# PC104Plus-ESP32-Module.net
KiCad netlist of a schematic drawn in Altium Designer
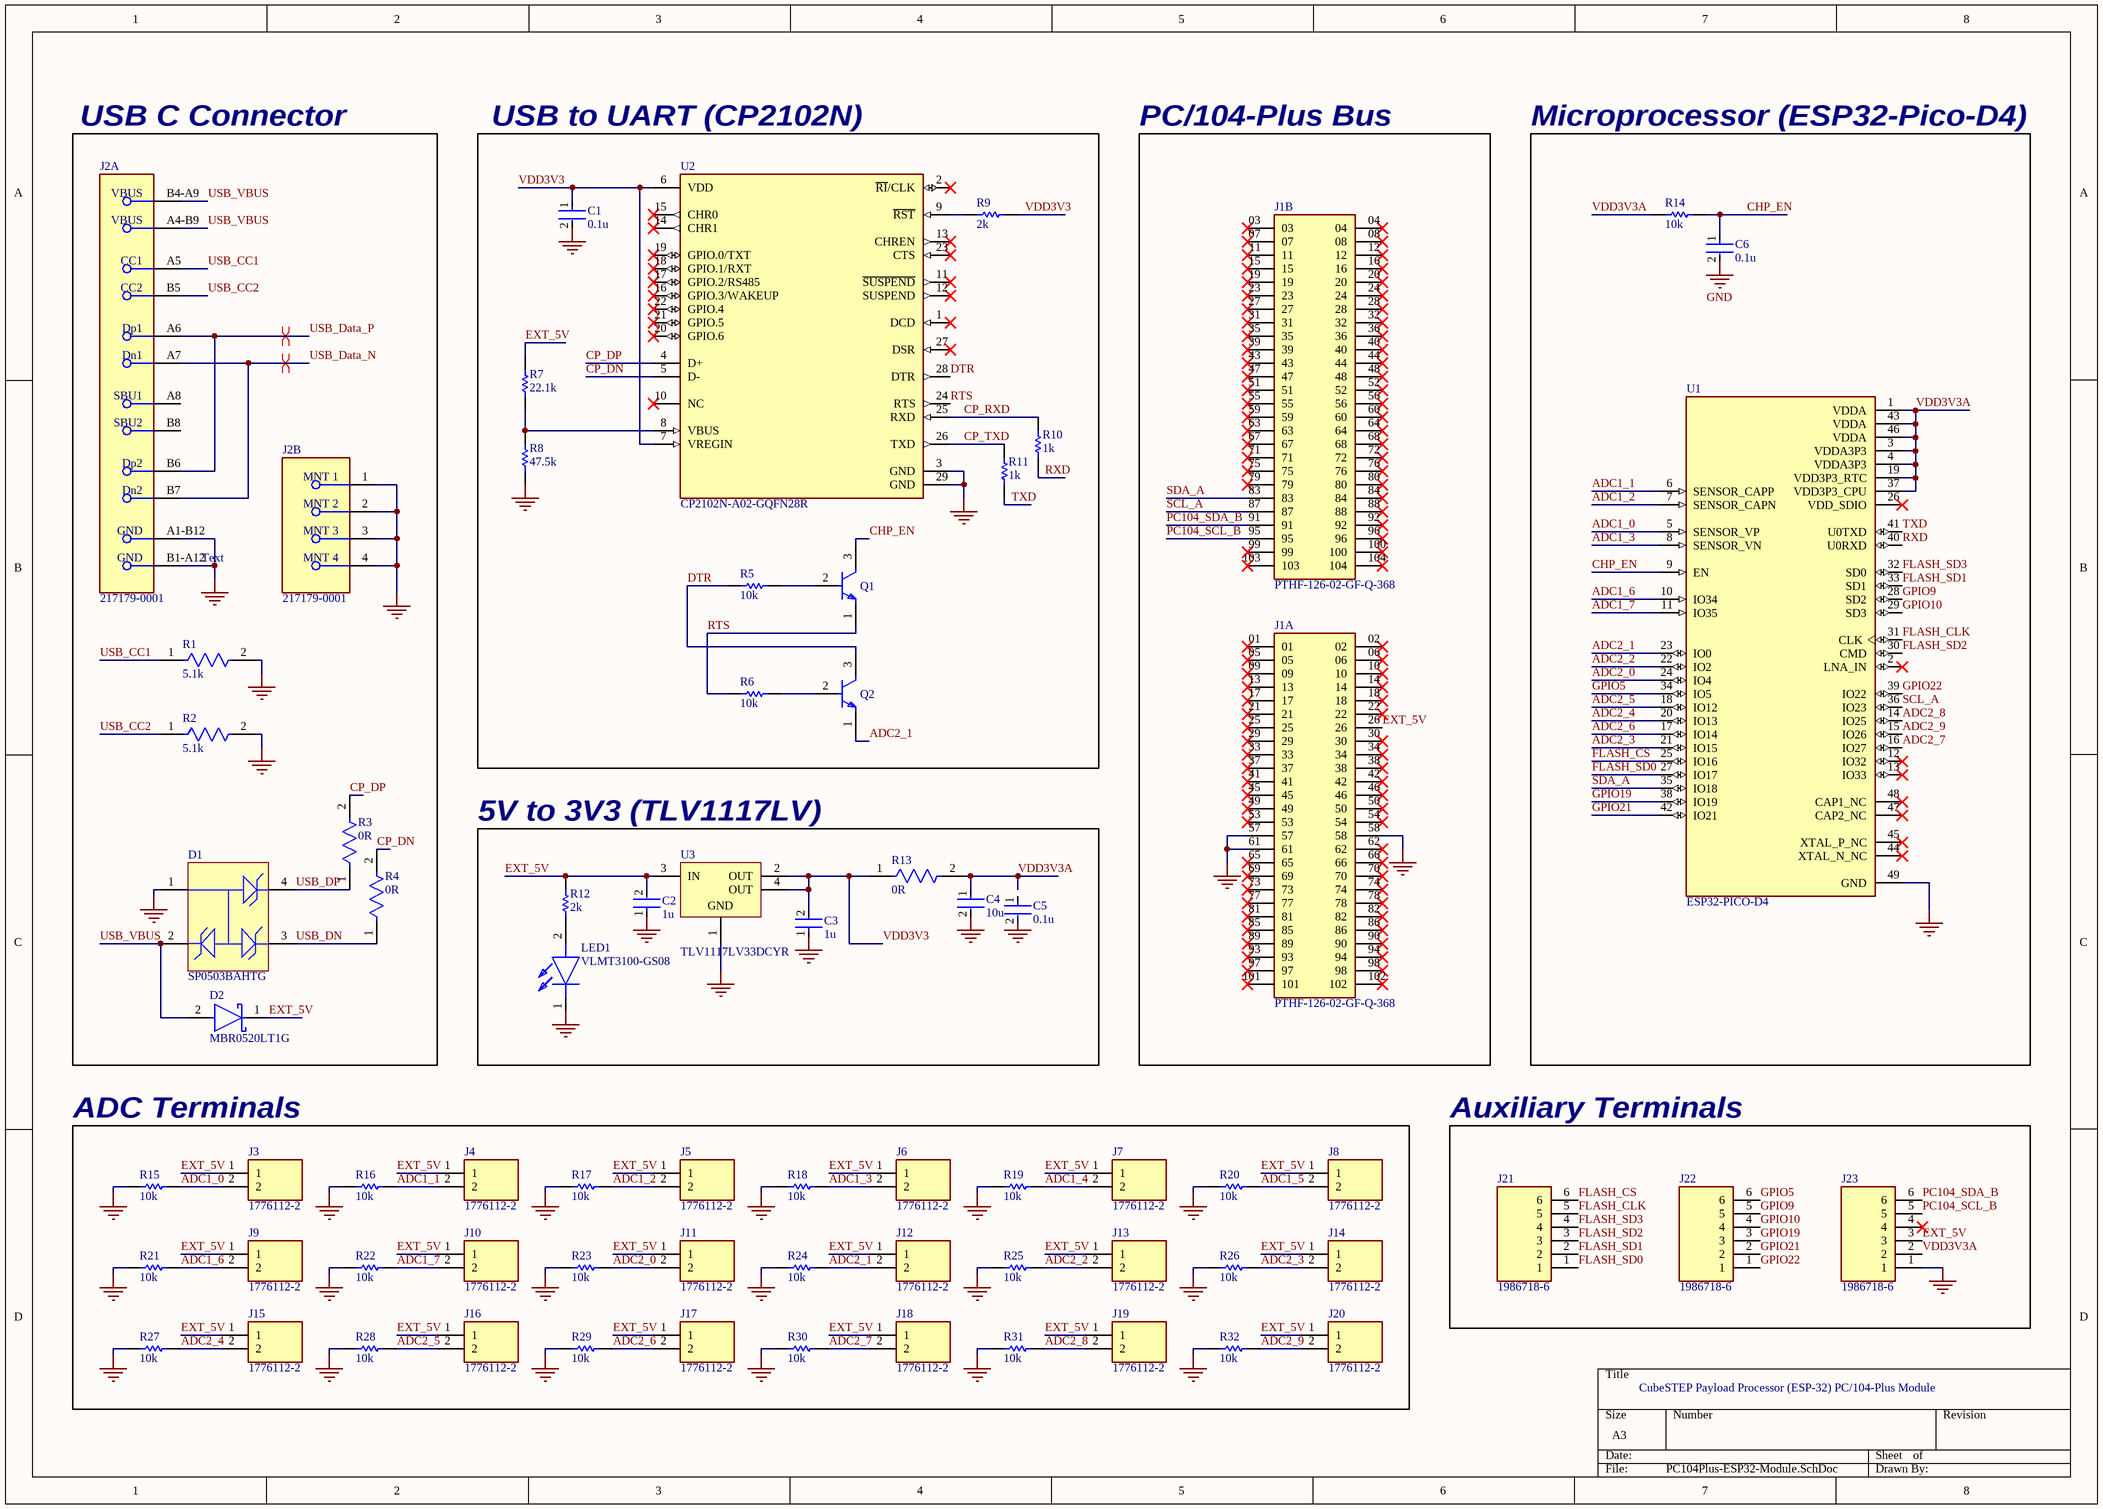
[diagram p0: PC104Plus-ESP32-Module.SchDoc]

(export (version "E")
  (design (tool "Eeschema 10.0.6"))
  (components
    (comp (ref "C1")
      (value "0.1u")
      (footprint "FP-CL31-IPC_B")
      (description "Cap Ceramic 1uF 50V X7R ±10% SMD 1206 +125°C Embossed T/R")
      (fields (field (name "VOLTAGE") "50V") (field (name "TOLERANCE") "10%"))
      (libsource (lib "Altium Content Vault") (part "b4654b650e69147ec39a6b967a45e02"))
    )
    (comp (ref "C2")
      (value "1u")
      (footprint "FP-CL10-IPC_C")
      (description "Cap Ceramic 1uF 10V X5R ±10% Pad SMD 0603 +85°C T/R")
      (fields (field (name "VOLTAGE") "10V") (field (name "TOLERANCE") "10%"))
      (libsource (lib "Altium Content Vault") (part "b4654b650e69147ec39a6b967a45e02"))
    )
    (comp (ref "C3")
      (value "1u")
      (footprint "FP-CL10-IPC_C")
      (description "Cap Ceramic 1uF 10V X5R ±10% Pad SMD 0603 +85°C T/R")
      (fields (field (name "VOLTAGE") "10V") (field (name "TOLERANCE") "10%"))
      (libsource (lib "Altium Content Vault") (part "b4654b650e69147ec39a6b967a45e02"))
    )
    (comp (ref "C4")
      (value "10u")
      (footprint "FP-CL21-IPC_A")
      (description "CL21 Series 0805 10uF 16V ±10% Tolerance X5R Multilayer Ceramic Chip Capacitor")
      (fields (field (name "TOLERANCE") "10%") (field (name "VOLTAGE") "16V"))
      (libsource (lib "Altium Content Vault") (part "b4654b650e69147ec39a6b967a45e02"))
    )
    (comp (ref "C5")
      (value "0.1u")
      (footprint "FP-CL31-IPC_B")
      (description "Cap Ceramic 1uF 50V X7R ±10% SMD 1206 +125°C Embossed T/R")
      (fields (field (name "VOLTAGE") "50V") (field (name "TOLERANCE") "10%"))
      (libsource (lib "Altium Content Vault") (part "b4654b650e69147ec39a6b967a45e02"))
    )
    (comp (ref "C6")
      (value "0.1u")
      (footprint "FP-CL31-IPC_B")
      (description "Cap Ceramic 1uF 50V X7R ±10% SMD 1206 +125°C Embossed T/R")
      (fields (field (name "VOLTAGE") "50V") (field (name "TOLERANCE") "10%"))
      (libsource (lib "Altium Content Vault") (part "b4654b650e69147ec39a6b967a45e02"))
    )
    (comp (ref "D1")
      (value "SP0503BAHTG")
      (footprint "LFUS-SOT143-4_V")
      (description "TVS Diode Array, 30 pF, 30 KV, -40 to 85 degC, 4-Pin SOT143, RoHS, Tape and Reel")
      (fields (field (name "MANUFACTURER") "Littelfuse"))
      (libsource (lib "Altium Content Vault") (part "LFUS-SP0503BAHTG-SOT143-4"))
    )
    (comp (ref "D2")
      (value "MBR0520LT1G")
      (footprint "FP-425-04-IPC_C")
      (description "DIODE SCHOTTKY 20V 500MA SOD123")
      (libsource (lib "Altium Content Vault") (part "1d6ec82d83fb6aee721767c19dac4b9"))
    )
    (comp (ref "J1")
      (value "PTHF-126-02-GF-Q-368")
      (footprint "SAMTEC_PTHF-126-02-GF-Q-368")
      (fields (field (name "MF") "{'manufacturer': u'Samtec'}"))
      (libsource (lib "SnapEDA_Library") (part "PTHF-126-02-GF-Q-368"))
    )
    (comp (ref "J2")
      (value "217179-0001")
      (footprint "FP-217179-0001-MFG")
      (description "CONN RCP USB2.0 TYP C 24P SMD RA")
      (libsource (lib "Altium Content Vault") (part "5f86746d156db037abd23105bb3dbc5"))
    )
    (comp (ref "J3")
      (value "1776112-2")
      (footprint "TE_1776112-2")
      (description "2P,3.50MM,SIDE ENTRY,HIGH TMP")
      (fields (field (name "DIGI-KEY_PART_NUMBER") "A97973-ND") (field (name "MF") "TE Connectivity"))
      (libsource (lib "1776112-2") (part "1776112-2"))
    )
    (comp (ref "J4")
      (value "1776112-2")
      (footprint "TE_1776112-2")
      (description "2P,3.50MM,SIDE ENTRY,HIGH TMP")
      (fields (field (name "DIGI-KEY_PART_NUMBER") "A97973-ND") (field (name "MF") "TE Connectivity"))
      (libsource (lib "1776112-2") (part "1776112-2"))
    )
    (comp (ref "J5")
      (value "1776112-2")
      (footprint "TE_1776112-2")
      (description "2P,3.50MM,SIDE ENTRY,HIGH TMP")
      (fields (field (name "DIGI-KEY_PART_NUMBER") "A97973-ND") (field (name "MF") "TE Connectivity"))
      (libsource (lib "1776112-2") (part "1776112-2"))
    )
    (comp (ref "J6")
      (value "1776112-2")
      (footprint "TE_1776112-2")
      (description "2P,3.50MM,SIDE ENTRY,HIGH TMP")
      (fields (field (name "DIGI-KEY_PART_NUMBER") "A97973-ND") (field (name "MF") "TE Connectivity"))
      (libsource (lib "1776112-2") (part "1776112-2"))
    )
    (comp (ref "J7")
      (value "1776112-2")
      (footprint "TE_1776112-2")
      (description "2P,3.50MM,SIDE ENTRY,HIGH TMP")
      (fields (field (name "DIGI-KEY_PART_NUMBER") "A97973-ND") (field (name "MF") "TE Connectivity"))
      (libsource (lib "1776112-2") (part "1776112-2"))
    )
    (comp (ref "J8")
      (value "1776112-2")
      (footprint "TE_1776112-2")
      (description "2P,3.50MM,SIDE ENTRY,HIGH TMP")
      (fields (field (name "DIGI-KEY_PART_NUMBER") "A97973-ND") (field (name "MF") "TE Connectivity"))
      (libsource (lib "1776112-2") (part "1776112-2"))
    )
    (comp (ref "J9")
      (value "1776112-2")
      (footprint "TE_1776112-2")
      (description "2P,3.50MM,SIDE ENTRY,HIGH TMP")
      (fields (field (name "DIGI-KEY_PART_NUMBER") "A97973-ND") (field (name "MF") "TE Connectivity"))
      (libsource (lib "1776112-2") (part "1776112-2"))
    )
    (comp (ref "J10")
      (value "1776112-2")
      (footprint "TE_1776112-2")
      (description "2P,3.50MM,SIDE ENTRY,HIGH TMP")
      (fields (field (name "DIGI-KEY_PART_NUMBER") "A97973-ND") (field (name "MF") "TE Connectivity"))
      (libsource (lib "1776112-2") (part "1776112-2"))
    )
    (comp (ref "J11")
      (value "1776112-2")
      (footprint "TE_1776112-2")
      (description "2P,3.50MM,SIDE ENTRY,HIGH TMP")
      (fields (field (name "DIGI-KEY_PART_NUMBER") "A97973-ND") (field (name "MF") "TE Connectivity"))
      (libsource (lib "1776112-2") (part "1776112-2"))
    )
    (comp (ref "J12")
      (value "1776112-2")
      (footprint "TE_1776112-2")
      (description "2P,3.50MM,SIDE ENTRY,HIGH TMP")
      (fields (field (name "DIGI-KEY_PART_NUMBER") "A97973-ND") (field (name "MF") "TE Connectivity"))
      (libsource (lib "1776112-2") (part "1776112-2"))
    )
    (comp (ref "J13")
      (value "1776112-2")
      (footprint "TE_1776112-2")
      (description "2P,3.50MM,SIDE ENTRY,HIGH TMP")
      (fields (field (name "DIGI-KEY_PART_NUMBER") "A97973-ND") (field (name "MF") "TE Connectivity"))
      (libsource (lib "1776112-2") (part "1776112-2"))
    )
    (comp (ref "J14")
      (value "1776112-2")
      (footprint "TE_1776112-2")
      (description "2P,3.50MM,SIDE ENTRY,HIGH TMP")
      (fields (field (name "DIGI-KEY_PART_NUMBER") "A97973-ND") (field (name "MF") "TE Connectivity"))
      (libsource (lib "1776112-2") (part "1776112-2"))
    )
    (comp (ref "J15")
      (value "1776112-2")
      (footprint "TE_1776112-2")
      (description "2P,3.50MM,SIDE ENTRY,HIGH TMP")
      (fields (field (name "DIGI-KEY_PART_NUMBER") "A97973-ND") (field (name "MF") "TE Connectivity"))
      (libsource (lib "1776112-2") (part "1776112-2"))
    )
    (comp (ref "J16")
      (value "1776112-2")
      (footprint "TE_1776112-2")
      (description "2P,3.50MM,SIDE ENTRY,HIGH TMP")
      (fields (field (name "DIGI-KEY_PART_NUMBER") "A97973-ND") (field (name "MF") "TE Connectivity"))
      (libsource (lib "1776112-2") (part "1776112-2"))
    )
    (comp (ref "J17")
      (value "1776112-2")
      (footprint "TE_1776112-2")
      (description "2P,3.50MM,SIDE ENTRY,HIGH TMP")
      (fields (field (name "DIGI-KEY_PART_NUMBER") "A97973-ND") (field (name "MF") "TE Connectivity"))
      (libsource (lib "1776112-2") (part "1776112-2"))
    )
    (comp (ref "J18")
      (value "1776112-2")
      (footprint "TE_1776112-2")
      (description "2P,3.50MM,SIDE ENTRY,HIGH TMP")
      (fields (field (name "DIGI-KEY_PART_NUMBER") "A97973-ND") (field (name "MF") "TE Connectivity"))
      (libsource (lib "1776112-2") (part "1776112-2"))
    )
    (comp (ref "J19")
      (value "1776112-2")
      (footprint "TE_1776112-2")
      (description "2P,3.50MM,SIDE ENTRY,HIGH TMP")
      (fields (field (name "DIGI-KEY_PART_NUMBER") "A97973-ND") (field (name "MF") "TE Connectivity"))
      (libsource (lib "1776112-2") (part "1776112-2"))
    )
    (comp (ref "J20")
      (value "1776112-2")
      (footprint "TE_1776112-2")
      (description "2P,3.50MM,SIDE ENTRY,HIGH TMP")
      (fields (field (name "DIGI-KEY_PART_NUMBER") "A97973-ND") (field (name "MF") "TE Connectivity"))
      (libsource (lib "1776112-2") (part "1776112-2"))
    )
    (comp (ref "J21")
      (value "1986718-6")
      (footprint "TE_1986718-6")
      (description "HEADER, 6P, 3.5 PCB 16.5 H WB")
      (fields (field (name "MF") "{'manufacturer': u'TE Connectivity'}"))
      (libsource (lib "SnapEDA_Library") (part "1986718-6"))
    )
    (comp (ref "J22")
      (value "1986718-6")
      (footprint "TE_1986718-6")
      (description "HEADER, 6P, 3.5 PCB 16.5 H WB")
      (fields (field (name "MF") "{'manufacturer': u'TE Connectivity'}"))
      (libsource (lib "SnapEDA_Library") (part "1986718-6"))
    )
    (comp (ref "J23")
      (value "1986718-6")
      (footprint "TE_1986718-6")
      (description "HEADER, 6P, 3.5 PCB 16.5 H WB")
      (fields (field (name "MF") "{'manufacturer': u'TE Connectivity'}"))
      (libsource (lib "SnapEDA_Library") (part "1986718-6"))
    )
    (comp (ref "LED1")
      (value "VLMT3100-GS08")
      (footprint "SamacSys:VLMT3100-GS08")
      (description "LED")
      (fields (field (name "MOUSER PART NUMBER") "78-VLMT3100"))
      (libsource (lib "*") (part "VLMT3100-GS08"))
    )
    (comp (ref "Q1")
      (value "SS8050CBU")
      (libsource (lib "Trans_ON_Semiconductor_SS8050CBU_eec") (part "SS8050CBU"))
    )
    (comp (ref "Q2")
      (value "SS8050CBU")
      (libsource (lib "Trans_ON_Semiconductor_SS8050CBU_eec") (part "SS8050CBU"))
    )
    (comp (ref "R1")
      (value "5.1k")
      (footprint "FP-ERJ3EK-MFG")
      (description "RES SMD 5.1K OHM 1% 1/10W 0603")
      (fields (field (name "TOLERANCE") "1%"))
      (libsource (lib "Altium Content Vault") (part "1029c3af85768c4190bb7ad29bc67b5"))
    )
    (comp (ref "R2")
      (value "5.1k")
      (footprint "FP-ERJ3EK-MFG")
      (description "RES SMD 5.1K OHM 1% 1/10W 0603")
      (fields (field (name "TOLERANCE") "1%"))
      (libsource (lib "Altium Content Vault") (part "1029c3af85768c4190bb7ad29bc67b5"))
    )
    (comp (ref "R3")
      (value "0R")
      (footprint "FP-ERJ1GN-MFG")
      (description "RES SMD 0 OHM JUMPER 1/20W 0201")
      (fields (field (name "TOLERANCE") "1%"))
      (libsource (lib "Altium Content Vault") (part "1029c3af85768c4190bb7ad29bc67b5"))
    )
    (comp (ref "R4")
      (value "0R")
      (footprint "FP-ERJ1GN-MFG")
      (description "RES SMD 0 OHM JUMPER 1/20W 0201")
      (fields (field (name "TOLERANCE") "1%"))
      (libsource (lib "Altium Content Vault") (part "1029c3af85768c4190bb7ad29bc67b5"))
    )
    (comp (ref "R5")
      (value "10k")
      (footprint "RESC1609X55X30LL15T15")
      (description "Chip Resistor, 10 KOhm, +/- 1%, 0.1 W, -55 to 155 degC, 0603 (1608 Metric), RoHS, Tape and Reel")
      (fields (field (name "TOLERANCE") "1%") (field (name "MANUFACTURER") "Panasonic"))
      (libsource (lib "Altium Content Vault") (part "RES-2"))
    )
    (comp (ref "R6")
      (value "10k")
      (footprint "RESC1609X55X30LL15T15")
      (description "Chip Resistor, 10 KOhm, +/- 1%, 0.1 W, -55 to 155 degC, 0603 (1608 Metric), RoHS, Tape and Reel")
      (fields (field (name "TOLERANCE") "1%") (field (name "MANUFACTURER") "Panasonic"))
      (libsource (lib "Altium Content Vault") (part "RES-2"))
    )
    (comp (ref "R7")
      (value "22.1k")
      (footprint "RESC2013X70X40NL20T20")
      (fields (field (name "PART NUMBER") "ERJ-6ENF2212V") (field (name "MANUFACTURER") "Panasonic"))
      (libsource (lib "Altium Content Vault") (part "RES"))
    )
    (comp (ref "R8")
      (value "47.5k")
      (footprint "RESC1005X40X25NL05T05")
      (fields (field (name "PART NUMBER") "ERJ-2RKF47R5X") (field (name "MANUFACTURER") "Panasonic"))
      (libsource (lib "Altium Content Vault") (part "RES"))
    )
    (comp (ref "R9")
      (value "2k")
      (footprint "RESC1005X40X25LL05T05")
      (fields (field (name "PART NUMBER") "ERJ-2GEJ202X") (field (name "MANUFACTURER") "Panasonic"))
      (libsource (lib "Altium Content Vault") (part "RES"))
    )
    (comp (ref "R10")
      (value "1k")
      (footprint "RESC2013X70X40ML20T20")
      (description "Chip Resistor, 1 KOhm, +/- 1%, 0.125 W, -55 to 155 degC, 0805 (2012 Metric), RoHS, Tape and Reel")
      (fields (field (name "MANUFACTURER") "Panasonic"))
      (libsource (lib "Altium Content Vault") (part "RES-2"))
    )
    (comp (ref "R11")
      (value "1k")
      (footprint "RESC2013X70X40ML20T20")
      (description "Chip Resistor, 1 KOhm, +/- 1%, 0.125 W, -55 to 155 degC, 0805 (2012 Metric), RoHS, Tape and Reel")
      (fields (field (name "MANUFACTURER") "Panasonic"))
      (libsource (lib "Altium Content Vault") (part "RES-2"))
    )
    (comp (ref "R12")
      (value "2k")
      (footprint "RESC1005X40X25LL05T05")
      (fields (field (name "PART NUMBER") "ERJ-2GEJ202X") (field (name "MANUFACTURER") "Panasonic"))
      (libsource (lib "Altium Content Vault") (part "RES"))
    )
    (comp (ref "R13")
      (value "0R")
      (footprint "FP-ERJ1GN-MFG")
      (description "RES SMD 0 OHM JUMPER 1/20W 0201")
      (fields (field (name "TOLERANCE") "1%"))
      (libsource (lib "Altium Content Vault") (part "1029c3af85768c4190bb7ad29bc67b5"))
    )
    (comp (ref "R14")
      (value "10k")
      (footprint "RESC1609X55X30LL15T15")
      (description "Chip Resistor, 10 KOhm, +/- 1%, 0.1 W, -55 to 155 degC, 0603 (1608 Metric), RoHS, Tape and Reel")
      (fields (field (name "TOLERANCE") "1%") (field (name "MANUFACTURER") "Panasonic"))
      (libsource (lib "Altium Content Vault") (part "RES-2"))
    )
    (comp (ref "R15")
      (value "10k")
      (footprint "RESC1609X55X30LL15T15")
      (description "Chip Resistor, 10 KOhm, +/- 1%, 0.1 W, -55 to 155 degC, 0603 (1608 Metric), RoHS, Tape and Reel")
      (fields (field (name "TOLERANCE") "1%") (field (name "MANUFACTURER") "Panasonic"))
      (libsource (lib "Altium Content Vault") (part "RES-2"))
    )
    (comp (ref "R16")
      (value "10k")
      (footprint "RESC1609X55X30LL15T15")
      (description "Chip Resistor, 10 KOhm, +/- 1%, 0.1 W, -55 to 155 degC, 0603 (1608 Metric), RoHS, Tape and Reel")
      (fields (field (name "TOLERANCE") "1%") (field (name "MANUFACTURER") "Panasonic"))
      (libsource (lib "Altium Content Vault") (part "RES-2"))
    )
    (comp (ref "R17")
      (value "10k")
      (footprint "RESC1609X55X30LL15T15")
      (description "Chip Resistor, 10 KOhm, +/- 1%, 0.1 W, -55 to 155 degC, 0603 (1608 Metric), RoHS, Tape and Reel")
      (fields (field (name "TOLERANCE") "1%") (field (name "MANUFACTURER") "Panasonic"))
      (libsource (lib "Altium Content Vault") (part "RES-2"))
    )
    (comp (ref "R18")
      (value "10k")
      (footprint "RESC1609X55X30LL15T15")
      (description "Chip Resistor, 10 KOhm, +/- 1%, 0.1 W, -55 to 155 degC, 0603 (1608 Metric), RoHS, Tape and Reel")
      (fields (field (name "TOLERANCE") "1%") (field (name "MANUFACTURER") "Panasonic"))
      (libsource (lib "Altium Content Vault") (part "RES-2"))
    )
    (comp (ref "R19")
      (value "10k")
      (footprint "RESC1609X55X30LL15T15")
      (description "Chip Resistor, 10 KOhm, +/- 1%, 0.1 W, -55 to 155 degC, 0603 (1608 Metric), RoHS, Tape and Reel")
      (fields (field (name "TOLERANCE") "1%") (field (name "MANUFACTURER") "Panasonic"))
      (libsource (lib "Altium Content Vault") (part "RES-2"))
    )
    (comp (ref "R20")
      (value "10k")
      (footprint "RESC1609X55X30LL15T15")
      (description "Chip Resistor, 10 KOhm, +/- 1%, 0.1 W, -55 to 155 degC, 0603 (1608 Metric), RoHS, Tape and Reel")
      (fields (field (name "TOLERANCE") "1%") (field (name "MANUFACTURER") "Panasonic"))
      (libsource (lib "Altium Content Vault") (part "RES-2"))
    )
    (comp (ref "R21")
      (value "10k")
      (footprint "RESC1609X55X30LL15T15")
      (description "Chip Resistor, 10 KOhm, +/- 1%, 0.1 W, -55 to 155 degC, 0603 (1608 Metric), RoHS, Tape and Reel")
      (fields (field (name "TOLERANCE") "1%") (field (name "MANUFACTURER") "Panasonic"))
      (libsource (lib "Altium Content Vault") (part "RES-2"))
    )
    (comp (ref "R22")
      (value "10k")
      (footprint "RESC1609X55X30LL15T15")
      (description "Chip Resistor, 10 KOhm, +/- 1%, 0.1 W, -55 to 155 degC, 0603 (1608 Metric), RoHS, Tape and Reel")
      (fields (field (name "TOLERANCE") "1%") (field (name "MANUFACTURER") "Panasonic"))
      (libsource (lib "Altium Content Vault") (part "RES-2"))
    )
    (comp (ref "R23")
      (value "10k")
      (footprint "RESC1609X55X30LL15T15")
      (description "Chip Resistor, 10 KOhm, +/- 1%, 0.1 W, -55 to 155 degC, 0603 (1608 Metric), RoHS, Tape and Reel")
      (fields (field (name "TOLERANCE") "1%") (field (name "MANUFACTURER") "Panasonic"))
      (libsource (lib "Altium Content Vault") (part "RES-2"))
    )
    (comp (ref "R24")
      (value "10k")
      (footprint "RESC1609X55X30LL15T15")
      (description "Chip Resistor, 10 KOhm, +/- 1%, 0.1 W, -55 to 155 degC, 0603 (1608 Metric), RoHS, Tape and Reel")
      (fields (field (name "TOLERANCE") "1%") (field (name "MANUFACTURER") "Panasonic"))
      (libsource (lib "Altium Content Vault") (part "RES-2"))
    )
    (comp (ref "R25")
      (value "10k")
      (footprint "RESC1609X55X30LL15T15")
      (description "Chip Resistor, 10 KOhm, +/- 1%, 0.1 W, -55 to 155 degC, 0603 (1608 Metric), RoHS, Tape and Reel")
      (fields (field (name "TOLERANCE") "1%") (field (name "MANUFACTURER") "Panasonic"))
      (libsource (lib "Altium Content Vault") (part "RES-2"))
    )
    (comp (ref "R26")
      (value "10k")
      (footprint "RESC1609X55X30LL15T15")
      (description "Chip Resistor, 10 KOhm, +/- 1%, 0.1 W, -55 to 155 degC, 0603 (1608 Metric), RoHS, Tape and Reel")
      (fields (field (name "TOLERANCE") "1%") (field (name "MANUFACTURER") "Panasonic"))
      (libsource (lib "Altium Content Vault") (part "RES-2"))
    )
    (comp (ref "R27")
      (value "10k")
      (footprint "RESC1609X55X30LL15T15")
      (description "Chip Resistor, 10 KOhm, +/- 1%, 0.1 W, -55 to 155 degC, 0603 (1608 Metric), RoHS, Tape and Reel")
      (fields (field (name "TOLERANCE") "1%") (field (name "MANUFACTURER") "Panasonic"))
      (libsource (lib "Altium Content Vault") (part "RES-2"))
    )
    (comp (ref "R28")
      (value "10k")
      (footprint "RESC1609X55X30LL15T15")
      (description "Chip Resistor, 10 KOhm, +/- 1%, 0.1 W, -55 to 155 degC, 0603 (1608 Metric), RoHS, Tape and Reel")
      (fields (field (name "TOLERANCE") "1%") (field (name "MANUFACTURER") "Panasonic"))
      (libsource (lib "Altium Content Vault") (part "RES-2"))
    )
    (comp (ref "R29")
      (value "10k")
      (footprint "RESC1609X55X30LL15T15")
      (description "Chip Resistor, 10 KOhm, +/- 1%, 0.1 W, -55 to 155 degC, 0603 (1608 Metric), RoHS, Tape and Reel")
      (fields (field (name "TOLERANCE") "1%") (field (name "MANUFACTURER") "Panasonic"))
      (libsource (lib "Altium Content Vault") (part "RES-2"))
    )
    (comp (ref "R30")
      (value "10k")
      (footprint "RESC1609X55X30LL15T15")
      (description "Chip Resistor, 10 KOhm, +/- 1%, 0.1 W, -55 to 155 degC, 0603 (1608 Metric), RoHS, Tape and Reel")
      (fields (field (name "TOLERANCE") "1%") (field (name "MANUFACTURER") "Panasonic"))
      (libsource (lib "Altium Content Vault") (part "RES-2"))
    )
    (comp (ref "R31")
      (value "10k")
      (footprint "RESC1609X55X30LL15T15")
      (description "Chip Resistor, 10 KOhm, +/- 1%, 0.1 W, -55 to 155 degC, 0603 (1608 Metric), RoHS, Tape and Reel")
      (fields (field (name "TOLERANCE") "1%") (field (name "MANUFACTURER") "Panasonic"))
      (libsource (lib "Altium Content Vault") (part "RES-2"))
    )
    (comp (ref "R32")
      (value "10k")
      (footprint "RESC1609X55X30LL15T15")
      (description "Chip Resistor, 10 KOhm, +/- 1%, 0.1 W, -55 to 155 degC, 0603 (1608 Metric), RoHS, Tape and Reel")
      (fields (field (name "TOLERANCE") "1%") (field (name "MANUFACTURER") "Panasonic"))
      (libsource (lib "Altium Content Vault") (part "RES-2"))
    )
    (comp (ref "U1")
      (value "ESP32-PICO-D4")
      (footprint "PQFN50P700X700X104-49N")
      (libsource (lib "ESP32-PICO-D4") (part "ESP32-PICO-D4"))
    )
    (comp (ref "U2")
      (value "CP2102N-A02-GQFN28R")
      (footprint "FP-CP2102N-A02-GQFN28R-MFG")
      (description "IC USB TO UART BRIDGE QFN28")
      (libsource (lib "Altium Content Vault") (part "670edaef084fb69d2a747396d70a05e"))
    )
    (comp (ref "U3")
      (value "TLV1117LV33DCYR")
      (footprint "DCY0004A_N")
      (fields (field (name "MANUFACTURER") "Texas Instruments"))
      (libsource (lib "Altium Content Vault") (part "TI-TLV1117LV33DCY4"))
    )
  )
  (nets
    (net (code "1") (name "/ADC1_0") (class "Default")
      (node (ref "J3") (pin "2") (pinfunction "2_2") (pintype "passive"))
      (node (ref "R15") (pin "1") (pinfunction "1_1") (pintype "passive"))
      (node (ref "U1") (pin "5") (pinfunction "SENSOR_VP_5") (pintype "input"))
    )
    (net (code "2") (name "/ADC1_1") (class "Default")
      (node (ref "J4") (pin "2") (pinfunction "2_2") (pintype "passive"))
      (node (ref "R16") (pin "1") (pinfunction "1_1") (pintype "passive"))
      (node (ref "U1") (pin "6") (pinfunction "SENSOR_CAPP_6") (pintype "input"))
    )
    (net (code "3") (name "/ADC1_2") (class "Default")
      (node (ref "J5") (pin "2") (pinfunction "2_2") (pintype "passive"))
      (node (ref "R17") (pin "1") (pinfunction "1_1") (pintype "passive"))
      (node (ref "U1") (pin "7") (pinfunction "SENSOR_CAPN_7") (pintype "input"))
    )
    (net (code "4") (name "/ADC1_3") (class "Default")
      (node (ref "J6") (pin "2") (pinfunction "2_2") (pintype "passive"))
      (node (ref "R18") (pin "1") (pinfunction "1_1") (pintype "passive"))
      (node (ref "U1") (pin "8") (pinfunction "SENSOR_VN_8") (pintype "input"))
    )
    (net (code "5") (name "/ADC1_4") (class "Default")
      (node (ref "J7") (pin "2") (pinfunction "2_2") (pintype "passive"))
      (node (ref "R19") (pin "1") (pinfunction "1_1") (pintype "passive"))
    )
    (net (code "6") (name "/ADC1_5") (class "Default")
      (node (ref "J8") (pin "2") (pinfunction "2_2") (pintype "passive"))
      (node (ref "R20") (pin "1") (pinfunction "1_1") (pintype "passive"))
    )
    (net (code "7") (name "/ADC1_6") (class "Default")
      (node (ref "J9") (pin "2") (pinfunction "2_2") (pintype "passive"))
      (node (ref "R21") (pin "1") (pinfunction "1_1") (pintype "passive"))
      (node (ref "U1") (pin "10") (pinfunction "IO34_10") (pintype "input"))
    )
    (net (code "8") (name "/ADC1_7") (class "Default")
      (node (ref "J10") (pin "2") (pinfunction "2_2") (pintype "passive"))
      (node (ref "R22") (pin "1") (pinfunction "1_1") (pintype "passive"))
      (node (ref "U1") (pin "11") (pinfunction "IO35_11") (pintype "input"))
    )
    (net (code "9") (name "/ADC2_0") (class "Default")
      (node (ref "J11") (pin "2") (pinfunction "2_2") (pintype "passive"))
      (node (ref "R23") (pin "1") (pinfunction "1_1") (pintype "passive"))
      (node (ref "U1") (pin "24") (pinfunction "IO4_24") (pintype "bidirectional"))
    )
    (net (code "10") (name "/ADC2_1") (class "Default")
      (node (ref "J12") (pin "2") (pinfunction "2_2") (pintype "passive"))
      (node (ref "Q2") (pin "1") (pinfunction "E_1") (pintype "passive"))
      (node (ref "R24") (pin "1") (pinfunction "1_1") (pintype "passive"))
      (node (ref "U1") (pin "23") (pinfunction "IO0_23") (pintype "bidirectional"))
    )
    (net (code "11") (name "/ADC2_2") (class "Default")
      (node (ref "J13") (pin "2") (pinfunction "2_2") (pintype "passive"))
      (node (ref "R25") (pin "1") (pinfunction "1_1") (pintype "passive"))
      (node (ref "U1") (pin "22") (pinfunction "IO2_22") (pintype "bidirectional"))
    )
    (net (code "12") (name "/ADC2_3") (class "Default")
      (node (ref "J14") (pin "2") (pinfunction "2_2") (pintype "passive"))
      (node (ref "R26") (pin "1") (pinfunction "1_1") (pintype "passive"))
      (node (ref "U1") (pin "21") (pinfunction "IO15_21") (pintype "bidirectional"))
    )
    (net (code "13") (name "/ADC2_4") (class "Default")
      (node (ref "J15") (pin "2") (pinfunction "2_2") (pintype "passive"))
      (node (ref "R27") (pin "1") (pinfunction "1_1") (pintype "passive"))
      (node (ref "U1") (pin "20") (pinfunction "IO13_20") (pintype "bidirectional"))
    )
    (net (code "14") (name "/ADC2_5") (class "Default")
      (node (ref "J16") (pin "2") (pinfunction "2_2") (pintype "passive"))
      (node (ref "R28") (pin "1") (pinfunction "1_1") (pintype "passive"))
      (node (ref "U1") (pin "18") (pinfunction "IO12_18") (pintype "bidirectional"))
    )
    (net (code "15") (name "/ADC2_6") (class "Default")
      (node (ref "J17") (pin "2") (pinfunction "2_2") (pintype "passive"))
      (node (ref "R29") (pin "1") (pinfunction "1_1") (pintype "passive"))
      (node (ref "U1") (pin "17") (pinfunction "IO14_17") (pintype "bidirectional"))
    )
    (net (code "16") (name "/ADC2_7") (class "Default")
      (node (ref "J18") (pin "2") (pinfunction "2_2") (pintype "passive"))
      (node (ref "R30") (pin "1") (pinfunction "1_1") (pintype "passive"))
      (node (ref "U1") (pin "16") (pinfunction "IO27_16") (pintype "bidirectional"))
    )
    (net (code "17") (name "/ADC2_8") (class "Default")
      (node (ref "J19") (pin "2") (pinfunction "2_2") (pintype "passive"))
      (node (ref "R31") (pin "1") (pinfunction "1_1") (pintype "passive"))
      (node (ref "U1") (pin "14") (pinfunction "IO25_14") (pintype "bidirectional"))
    )
    (net (code "18") (name "/ADC2_9") (class "Default")
      (node (ref "J20") (pin "2") (pinfunction "2_2") (pintype "passive"))
      (node (ref "R32") (pin "1") (pinfunction "1_1") (pintype "passive"))
      (node (ref "U1") (pin "15") (pinfunction "IO26_15") (pintype "bidirectional"))
    )
    (net (code "19") (name "/CHP_EN") (class "Default")
      (node (ref "C6") (pin "1") (pinfunction "1_1") (pintype "passive"))
      (node (ref "Q1") (pin "3") (pinfunction "C_3") (pintype "passive"))
      (node (ref "R14") (pin "1") (pinfunction "1_1") (pintype "passive"))
      (node (ref "U1") (pin "9") (pinfunction "EN_9") (pintype "input"))
    )
    (net (code "20") (name "/CP_DN") (class "Default")
      (node (ref "R4") (pin "2") (pinfunction "2_2") (pintype "passive"))
      (node (ref "U2") (pin "5") (pinfunction "D-_5") (pintype "passive"))
    )
    (net (code "21") (name "/CP_DP") (class "Default")
      (node (ref "R3") (pin "2") (pinfunction "2_2") (pintype "passive"))
      (node (ref "U2") (pin "4") (pinfunction "D+_4") (pintype "passive"))
    )
    (net (code "22") (name "/CP_RXD") (class "Default")
      (node (ref "R10") (pin "1") (pinfunction "1_1") (pintype "passive"))
      (node (ref "U2") (pin "25") (pinfunction "RXD_25") (pintype "input"))
    )
    (net (code "23") (name "/CP_TXD") (class "Default")
      (node (ref "R11") (pin "1") (pinfunction "1_1") (pintype "passive"))
      (node (ref "U2") (pin "26") (pinfunction "TXD_26") (pintype "output"))
    )
    (net (code "24") (name "/DTR") (class "Default")
      (node (ref "Q2") (pin "3") (pinfunction "C_3") (pintype "passive"))
      (node (ref "R5") (pin "2") (pinfunction "2_2") (pintype "passive"))
      (node (ref "U2") (pin "28") (pinfunction "DTR_28") (pintype "output"))
    )
    (net (code "25") (name "/EXT_5V") (class "Default")
      (node (ref "C2") (pin "2") (pinfunction "2_2") (pintype "passive"))
      (node (ref "D2") (pin "1") (pinfunction "C_1") (pintype "passive"))
      (node (ref "J1") (pin "26") (pinfunction "26_26") (pintype "passive"))
      (node (ref "J10") (pin "1") (pinfunction "1_1") (pintype "passive"))
      (node (ref "J11") (pin "1") (pinfunction "1_1") (pintype "passive"))
      (node (ref "J12") (pin "1") (pinfunction "1_1") (pintype "passive"))
      (node (ref "J13") (pin "1") (pinfunction "1_1") (pintype "passive"))
      (node (ref "J14") (pin "1") (pinfunction "1_1") (pintype "passive"))
      (node (ref "J15") (pin "1") (pinfunction "1_1") (pintype "passive"))
      (node (ref "J16") (pin "1") (pinfunction "1_1") (pintype "passive"))
      (node (ref "J17") (pin "1") (pinfunction "1_1") (pintype "passive"))
      (node (ref "J18") (pin "1") (pinfunction "1_1") (pintype "passive"))
      (node (ref "J19") (pin "1") (pinfunction "1_1") (pintype "passive"))
      (node (ref "J20") (pin "1") (pinfunction "1_1") (pintype "passive"))
      (node (ref "J23") (pin "3") (pinfunction "3_3") (pintype "passive"))
      (node (ref "J3") (pin "1") (pinfunction "1_1") (pintype "passive"))
      (node (ref "J4") (pin "1") (pinfunction "1_1") (pintype "passive"))
      (node (ref "J5") (pin "1") (pinfunction "1_1") (pintype "passive"))
      (node (ref "J6") (pin "1") (pinfunction "1_1") (pintype "passive"))
      (node (ref "J7") (pin "1") (pinfunction "1_1") (pintype "passive"))
      (node (ref "J8") (pin "1") (pinfunction "1_1") (pintype "passive"))
      (node (ref "J9") (pin "1") (pinfunction "1_1") (pintype "passive"))
      (node (ref "R12") (pin "2") (pinfunction "2_2") (pintype "passive"))
      (node (ref "R7") (pin "2") (pinfunction "2_2") (pintype "passive"))
      (node (ref "U3") (pin "3") (pinfunction "IN_3") (pintype "power_in"))
    )
    (net (code "26") (name "/FLASH_CLK") (class "Default")
      (node (ref "J21") (pin "5") (pinfunction "5_5") (pintype "passive"))
      (node (ref "U1") (pin "31") (pinfunction "CLK_31") (pintype "bidirectional"))
    )
    (net (code "27") (name "/FLASH_CS") (class "Default")
      (node (ref "J21") (pin "6") (pinfunction "6_6") (pintype "passive"))
      (node (ref "U1") (pin "25") (pinfunction "IO16_25") (pintype "bidirectional"))
    )
    (net (code "28") (name "/FLASH_SD0") (class "Default")
      (node (ref "J21") (pin "1") (pinfunction "1_1") (pintype "passive"))
      (node (ref "U1") (pin "27") (pinfunction "IO17_27") (pintype "bidirectional"))
    )
    (net (code "29") (name "/FLASH_SD1") (class "Default")
      (node (ref "J21") (pin "2") (pinfunction "2_2") (pintype "passive"))
      (node (ref "U1") (pin "33") (pinfunction "SD1_33") (pintype "bidirectional"))
    )
    (net (code "30") (name "/FLASH_SD2") (class "Default")
      (node (ref "J21") (pin "3") (pinfunction "3_3") (pintype "passive"))
      (node (ref "U1") (pin "30") (pinfunction "CMD_30") (pintype "bidirectional"))
    )
    (net (code "31") (name "/FLASH_SD3") (class "Default")
      (node (ref "J21") (pin "4") (pinfunction "4_4") (pintype "passive"))
      (node (ref "U1") (pin "32") (pinfunction "SD0_32") (pintype "bidirectional"))
    )
    (net (code "32") (name "/GPIO5") (class "Default")
      (node (ref "J22") (pin "6") (pinfunction "6_6") (pintype "passive"))
      (node (ref "U1") (pin "34") (pinfunction "IO5_34") (pintype "bidirectional"))
    )
    (net (code "33") (name "/GPIO9") (class "Default")
      (node (ref "J22") (pin "5") (pinfunction "5_5") (pintype "passive"))
      (node (ref "U1") (pin "28") (pinfunction "SD2_28") (pintype "bidirectional"))
    )
    (net (code "34") (name "/GPIO10") (class "Default")
      (node (ref "J22") (pin "4") (pinfunction "4_4") (pintype "passive"))
      (node (ref "U1") (pin "29") (pinfunction "SD3_29") (pintype "bidirectional"))
    )
    (net (code "35") (name "/GPIO19") (class "Default")
      (node (ref "J22") (pin "3") (pinfunction "3_3") (pintype "passive"))
      (node (ref "U1") (pin "38") (pinfunction "IO19_38") (pintype "bidirectional"))
    )
    (net (code "36") (name "/GPIO21") (class "Default")
      (node (ref "J22") (pin "2") (pinfunction "2_2") (pintype "passive"))
      (node (ref "U1") (pin "42") (pinfunction "IO21_42") (pintype "bidirectional"))
    )
    (net (code "37") (name "/GPIO22") (class "Default")
      (node (ref "J22") (pin "1") (pinfunction "1_1") (pintype "passive"))
      (node (ref "U1") (pin "39") (pinfunction "IO22_39") (pintype "bidirectional"))
    )
    (net (code "38") (name "/PC104_SCL_B") (class "Default")
      (node (ref "J1") (pin "95") (pinfunction "95_95") (pintype "passive"))
      (node (ref "J23") (pin "5") (pinfunction "5_5") (pintype "passive"))
    )
    (net (code "39") (name "/PC104_SDA_B") (class "Default")
      (node (ref "J1") (pin "91") (pinfunction "91_91") (pintype "passive"))
      (node (ref "J23") (pin "6") (pinfunction "6_6") (pintype "passive"))
    )
    (net (code "40") (name "/RTS") (class "Default")
      (node (ref "Q1") (pin "1") (pinfunction "E_1") (pintype "passive"))
      (node (ref "R6") (pin "2") (pinfunction "2_2") (pintype "passive"))
      (node (ref "U2") (pin "24") (pinfunction "RTS_24") (pintype "output"))
    )
    (net (code "41") (name "/RXD") (class "Default")
      (node (ref "R10") (pin "2") (pinfunction "2_2") (pintype "passive"))
      (node (ref "U1") (pin "40") (pinfunction "U0RXD_40") (pintype "bidirectional"))
    )
    (net (code "42") (name "/SCL_A") (class "Default")
      (node (ref "J1") (pin "87") (pinfunction "87_87") (pintype "passive"))
      (node (ref "U1") (pin "36") (pinfunction "IO23_36") (pintype "bidirectional"))
    )
    (net (code "43") (name "/SDA_A") (class "Default")
      (node (ref "J1") (pin "83") (pinfunction "83_83") (pintype "passive"))
      (node (ref "U1") (pin "35") (pinfunction "IO18_35") (pintype "bidirectional"))
    )
    (net (code "44") (name "/TXD") (class "Default")
      (node (ref "R11") (pin "2") (pinfunction "2_2") (pintype "passive"))
      (node (ref "U1") (pin "41") (pinfunction "U0TXD_41") (pintype "bidirectional"))
    )
    (net (code "45") (name "/USB_CC1") (class "Default")
      (node (ref "J2") (pin "A5") (pinfunction "CC1_A5") (pintype "passive"))
      (node (ref "R1") (pin "1") (pinfunction "1_1") (pintype "passive"))
    )
    (net (code "46") (name "/USB_CC2") (class "Default")
      (node (ref "J2") (pin "B5") (pinfunction "CC2_B5") (pintype "passive"))
      (node (ref "R2") (pin "1") (pinfunction "1_1") (pintype "passive"))
    )
    (net (code "47") (name "/USB_DN") (class "Default")
      (node (ref "D1") (pin "3") (pinfunction "3_3") (pintype "passive"))
      (node (ref "R4") (pin "1") (pinfunction "1_1") (pintype "passive"))
    )
    (net (code "48") (name "/USB_DP") (class "Default")
      (node (ref "D1") (pin "4") (pinfunction "4_4") (pintype "passive"))
      (node (ref "R3") (pin "1") (pinfunction "1_1") (pintype "passive"))
    )
    (net (code "49") (name "/USB_Data_N") (class "Default")
      (node (ref "J2") (pin "A7") (pinfunction "Dn1_A7") (pintype "passive"))
      (node (ref "J2") (pin "B7") (pinfunction "Dn2_B7") (pintype "passive"))
    )
    (net (code "50") (name "/USB_Data_P") (class "Default")
      (node (ref "J2") (pin "A6") (pinfunction "Dp1_A6") (pintype "passive"))
      (node (ref "J2") (pin "B6") (pinfunction "Dp2_B6") (pintype "passive"))
    )
    (net (code "51") (name "/USB_VBUS") (class "Default")
      (node (ref "D1") (pin "2") (pinfunction "2_2") (pintype "passive"))
      (node (ref "D2") (pin "2") (pinfunction "A_2") (pintype "passive"))
      (node (ref "J2") (pin "A4-B9") (pinfunction "VBUS_A4-B9") (pintype "power_in"))
      (node (ref "J2") (pin "B4-A9") (pinfunction "VBUS_B4-A9") (pintype "power_in"))
    )
    (net (code "52") (name "/VDD3V3") (class "Default")
      (node (ref "C1") (pin "1") (pinfunction "1_1") (pintype "passive"))
      (node (ref "C3") (pin "2") (pinfunction "2_2") (pintype "passive"))
      (node (ref "R13") (pin "1") (pinfunction "1_1") (pintype "passive"))
      (node (ref "R9") (pin "2") (pinfunction "2_2") (pintype "passive"))
      (node (ref "U2") (pin "6") (pinfunction "VDD_6") (pintype "power_in"))
      (node (ref "U2") (pin "7") (pinfunction "VREGIN_7") (pintype "input"))
      (node (ref "U3") (pin "2") (pinfunction "OUT_2") (pintype "power_in"))
      (node (ref "U3") (pin "4") (pinfunction "OUT_4") (pintype "power_in"))
    )
    (net (code "53") (name "/VDD3V3A") (class "Default")
      (node (ref "C4") (pin "1") (pinfunction "1_1") (pintype "passive"))
      (node (ref "J23") (pin "2") (pinfunction "2_2") (pintype "passive"))
      (node (ref "R13") (pin "2") (pinfunction "2_2") (pintype "passive"))
      (node (ref "R14") (pin "2") (pinfunction "2_2") (pintype "passive"))
      (node (ref "U1") (pin "1") (pinfunction "VDDA_1") (pintype "power_in"))
      (node (ref "U1") (pin "19") (pinfunction "VDD3P3_RTC_19") (pintype "power_in"))
      (node (ref "U1") (pin "3") (pinfunction "VDDA3P3_3") (pintype "power_in"))
      (node (ref "U1") (pin "37") (pinfunction "VDD3P3_CPU_37") (pintype "power_in"))
      (node (ref "U1") (pin "4") (pinfunction "VDDA3P3_4") (pintype "power_in"))
      (node (ref "U1") (pin "43") (pinfunction "VDDA_43") (pintype "power_in"))
      (node (ref "U1") (pin "46") (pinfunction "VDDA_46") (pintype "power_in"))
    )
    (net (code "54") (name "GND") (class "Default")
      (node (ref "C1") (pin "2") (pinfunction "2_2") (pintype "passive"))
      (node (ref "C2") (pin "1") (pinfunction "1_1") (pintype "passive"))
      (node (ref "C3") (pin "1") (pinfunction "1_1") (pintype "passive"))
      (node (ref "C4") (pin "2") (pinfunction "2_2") (pintype "passive"))
      (node (ref "C5") (pin "2") (pinfunction "2_2") (pintype "passive"))
      (node (ref "C6") (pin "2") (pinfunction "2_2") (pintype "passive"))
      (node (ref "D1") (pin "1") (pinfunction "1_1") (pintype "passive"))
      (node (ref "J1") (pin "57") (pinfunction "57_57") (pintype "passive"))
      (node (ref "J1") (pin "58") (pinfunction "58_58") (pintype "passive"))
      (node (ref "J1") (pin "61") (pinfunction "61_61") (pintype "passive"))
      (node (ref "J2") (pin "1") (pinfunction "MNT_1_1") (pintype "passive"))
      (node (ref "J2") (pin "2") (pinfunction "MNT_2_2") (pintype "passive"))
      (node (ref "J2") (pin "3") (pinfunction "MNT_3_3") (pintype "passive"))
      (node (ref "J2") (pin "4") (pinfunction "MNT_4_4") (pintype "passive"))
      (node (ref "J2") (pin "A1-B12") (pinfunction "GND_A1-B12") (pintype "power_in"))
      (node (ref "J2") (pin "B1-A12") (pinfunction "GND_B1-A12") (pintype "power_in"))
      (node (ref "J23") (pin "1") (pinfunction "1_1") (pintype "passive"))
      (node (ref "LED1") (pin "1") (pinfunction "K_1") (pintype "passive"))
      (node (ref "R1") (pin "2") (pinfunction "2_2") (pintype "passive"))
      (node (ref "R15") (pin "2") (pinfunction "2_2") (pintype "passive"))
      (node (ref "R16") (pin "2") (pinfunction "2_2") (pintype "passive"))
      (node (ref "R17") (pin "2") (pinfunction "2_2") (pintype "passive"))
      (node (ref "R18") (pin "2") (pinfunction "2_2") (pintype "passive"))
      (node (ref "R19") (pin "2") (pinfunction "2_2") (pintype "passive"))
      (node (ref "R2") (pin "2") (pinfunction "2_2") (pintype "passive"))
      (node (ref "R20") (pin "2") (pinfunction "2_2") (pintype "passive"))
      (node (ref "R21") (pin "2") (pinfunction "2_2") (pintype "passive"))
      (node (ref "R22") (pin "2") (pinfunction "2_2") (pintype "passive"))
      (node (ref "R23") (pin "2") (pinfunction "2_2") (pintype "passive"))
      (node (ref "R24") (pin "2") (pinfunction "2_2") (pintype "passive"))
      (node (ref "R25") (pin "2") (pinfunction "2_2") (pintype "passive"))
      (node (ref "R26") (pin "2") (pinfunction "2_2") (pintype "passive"))
      (node (ref "R27") (pin "2") (pinfunction "2_2") (pintype "passive"))
      (node (ref "R28") (pin "2") (pinfunction "2_2") (pintype "passive"))
      (node (ref "R29") (pin "2") (pinfunction "2_2") (pintype "passive"))
      (node (ref "R30") (pin "2") (pinfunction "2_2") (pintype "passive"))
      (node (ref "R31") (pin "2") (pinfunction "2_2") (pintype "passive"))
      (node (ref "R32") (pin "2") (pinfunction "2_2") (pintype "passive"))
      (node (ref "R8") (pin "1") (pinfunction "1_1") (pintype "passive"))
      (node (ref "U1") (pin "49") (pinfunction "GND_49") (pintype "power_in"))
      (node (ref "U2") (pin "29") (pinfunction "GND_29") (pintype "power_in"))
      (node (ref "U2") (pin "3") (pinfunction "GND_3") (pintype "power_in"))
      (node (ref "U3") (pin "1") (pinfunction "GND_1") (pintype "power_in"))
    )
    (net (code "55") (name "Net-(LED1-A)") (class "Default")
      (node (ref "LED1") (pin "2") (pinfunction "A_2") (pintype "passive"))
      (node (ref "R12") (pin "1") (pinfunction "1_1") (pintype "passive"))
    )
    (net (code "56") (name "Net-(Q1-B)") (class "Default")
      (node (ref "Q1") (pin "2") (pinfunction "B_2") (pintype "passive"))
      (node (ref "R5") (pin "1") (pinfunction "1_1") (pintype "passive"))
    )
    (net (code "57") (name "Net-(Q2-B)") (class "Default")
      (node (ref "Q2") (pin "2") (pinfunction "B_2") (pintype "passive"))
      (node (ref "R6") (pin "1") (pinfunction "1_1") (pintype "passive"))
    )
    (net (code "58") (name "Net-(U2-VBUS)") (class "Default")
      (node (ref "R7") (pin "1") (pinfunction "1_1") (pintype "passive"))
      (node (ref "R8") (pin "2") (pinfunction "2_2") (pintype "passive"))
      (node (ref "U2") (pin "8") (pinfunction "VBUS_8") (pintype "input"))
    )
    (net (code "59") (name "Net-(U2-~{RST})") (class "Default")
      (node (ref "R9") (pin "1") (pinfunction "1_1") (pintype "passive"))
      (node (ref "U2") (pin "9") (pinfunction "~{RST}_9") (pintype "input"))
    )
    (net (code "60") (name "unconnected-(C5-Pad1)") (class "Default")
      (node (ref "C5") (pin "1") (pinfunction "1_1") (pintype "passive"))
    )
    (net (code "61") (name "unconnected-(J1-Pad01)") (class "Default")
      (node (ref "J1") (pin "01") (pinfunction "01_01") (pintype "passive+no_connect"))
    )
    (net (code "62") (name "unconnected-(J1-Pad02)") (class "Default")
      (node (ref "J1") (pin "02") (pinfunction "02_02") (pintype "passive+no_connect"))
    )
    (net (code "63") (name "unconnected-(J1-Pad03)") (class "Default")
      (node (ref "J1") (pin "03") (pinfunction "03_03") (pintype "passive+no_connect"))
    )
    (net (code "64") (name "unconnected-(J1-Pad04)") (class "Default")
      (node (ref "J1") (pin "04") (pinfunction "04_04") (pintype "passive+no_connect"))
    )
    (net (code "65") (name "unconnected-(J1-Pad05)") (class "Default")
      (node (ref "J1") (pin "05") (pinfunction "05_05") (pintype "passive+no_connect"))
    )
    (net (code "66") (name "unconnected-(J1-Pad06)") (class "Default")
      (node (ref "J1") (pin "06") (pinfunction "06_06") (pintype "passive+no_connect"))
    )
    (net (code "67") (name "unconnected-(J1-Pad07)") (class "Default")
      (node (ref "J1") (pin "07") (pinfunction "07_07") (pintype "passive+no_connect"))
    )
    (net (code "68") (name "unconnected-(J1-Pad08)") (class "Default")
      (node (ref "J1") (pin "08") (pinfunction "08_08") (pintype "passive+no_connect"))
    )
    (net (code "69") (name "unconnected-(J1-Pad09)") (class "Default")
      (node (ref "J1") (pin "09") (pinfunction "09_09") (pintype "passive+no_connect"))
    )
    (net (code "70") (name "unconnected-(J1-Pad10)") (class "Default")
      (node (ref "J1") (pin "10") (pinfunction "10_10") (pintype "passive+no_connect"))
    )
    (net (code "71") (name "unconnected-(J1-Pad11)") (class "Default")
      (node (ref "J1") (pin "11") (pinfunction "11_11") (pintype "passive+no_connect"))
    )
    (net (code "72") (name "unconnected-(J1-Pad12)") (class "Default")
      (node (ref "J1") (pin "12") (pinfunction "12_12") (pintype "passive+no_connect"))
    )
    (net (code "73") (name "unconnected-(J1-Pad13)") (class "Default")
      (node (ref "J1") (pin "13") (pinfunction "13_13") (pintype "passive+no_connect"))
    )
    (net (code "74") (name "unconnected-(J1-Pad14)") (class "Default")
      (node (ref "J1") (pin "14") (pinfunction "14_14") (pintype "passive+no_connect"))
    )
    (net (code "75") (name "unconnected-(J1-Pad15)") (class "Default")
      (node (ref "J1") (pin "15") (pinfunction "15_15") (pintype "passive+no_connect"))
    )
    (net (code "76") (name "unconnected-(J1-Pad16)") (class "Default")
      (node (ref "J1") (pin "16") (pinfunction "16_16") (pintype "passive+no_connect"))
    )
    (net (code "77") (name "unconnected-(J1-Pad17)") (class "Default")
      (node (ref "J1") (pin "17") (pinfunction "17_17") (pintype "passive+no_connect"))
    )
    (net (code "78") (name "unconnected-(J1-Pad18)") (class "Default")
      (node (ref "J1") (pin "18") (pinfunction "18_18") (pintype "passive+no_connect"))
    )
    (net (code "79") (name "unconnected-(J1-Pad19)") (class "Default")
      (node (ref "J1") (pin "19") (pinfunction "19_19") (pintype "passive+no_connect"))
    )
    (net (code "80") (name "unconnected-(J1-Pad20)") (class "Default")
      (node (ref "J1") (pin "20") (pinfunction "20_20") (pintype "passive+no_connect"))
    )
    (net (code "81") (name "unconnected-(J1-Pad21)") (class "Default")
      (node (ref "J1") (pin "21") (pinfunction "21_21") (pintype "passive+no_connect"))
    )
    (net (code "82") (name "unconnected-(J1-Pad22)") (class "Default")
      (node (ref "J1") (pin "22") (pinfunction "22_22") (pintype "passive+no_connect"))
    )
    (net (code "83") (name "unconnected-(J1-Pad23)") (class "Default")
      (node (ref "J1") (pin "23") (pinfunction "23_23") (pintype "passive+no_connect"))
    )
    (net (code "84") (name "unconnected-(J1-Pad24)") (class "Default")
      (node (ref "J1") (pin "24") (pinfunction "24_24") (pintype "passive+no_connect"))
    )
    (net (code "85") (name "unconnected-(J1-Pad25)") (class "Default")
      (node (ref "J1") (pin "25") (pinfunction "25_25") (pintype "passive+no_connect"))
    )
    (net (code "86") (name "unconnected-(J1-Pad27)") (class "Default")
      (node (ref "J1") (pin "27") (pinfunction "27_27") (pintype "passive+no_connect"))
    )
    (net (code "87") (name "unconnected-(J1-Pad28)") (class "Default")
      (node (ref "J1") (pin "28") (pinfunction "28_28") (pintype "passive+no_connect"))
    )
    (net (code "88") (name "unconnected-(J1-Pad29)") (class "Default")
      (node (ref "J1") (pin "29") (pinfunction "29_29") (pintype "passive+no_connect"))
    )
    (net (code "89") (name "unconnected-(J1-Pad30)") (class "Default")
      (node (ref "J1") (pin "30") (pinfunction "30_30") (pintype "passive+no_connect"))
    )
    (net (code "90") (name "unconnected-(J1-Pad31)") (class "Default")
      (node (ref "J1") (pin "31") (pinfunction "31_31") (pintype "passive+no_connect"))
    )
    (net (code "91") (name "unconnected-(J1-Pad32)") (class "Default")
      (node (ref "J1") (pin "32") (pinfunction "32_32") (pintype "passive+no_connect"))
    )
    (net (code "92") (name "unconnected-(J1-Pad33)") (class "Default")
      (node (ref "J1") (pin "33") (pinfunction "33_33") (pintype "passive+no_connect"))
    )
    (net (code "93") (name "unconnected-(J1-Pad34)") (class "Default")
      (node (ref "J1") (pin "34") (pinfunction "34_34") (pintype "passive+no_connect"))
    )
    (net (code "94") (name "unconnected-(J1-Pad35)") (class "Default")
      (node (ref "J1") (pin "35") (pinfunction "35_35") (pintype "passive+no_connect"))
    )
    (net (code "95") (name "unconnected-(J1-Pad36)") (class "Default")
      (node (ref "J1") (pin "36") (pinfunction "36_36") (pintype "passive+no_connect"))
    )
    (net (code "96") (name "unconnected-(J1-Pad37)") (class "Default")
      (node (ref "J1") (pin "37") (pinfunction "37_37") (pintype "passive+no_connect"))
    )
    (net (code "97") (name "unconnected-(J1-Pad38)") (class "Default")
      (node (ref "J1") (pin "38") (pinfunction "38_38") (pintype "passive+no_connect"))
    )
    (net (code "98") (name "unconnected-(J1-Pad39)") (class "Default")
      (node (ref "J1") (pin "39") (pinfunction "39_39") (pintype "passive+no_connect"))
    )
    (net (code "99") (name "unconnected-(J1-Pad40)") (class "Default")
      (node (ref "J1") (pin "40") (pinfunction "40_40") (pintype "passive+no_connect"))
    )
    (net (code "100") (name "unconnected-(J1-Pad41)") (class "Default")
      (node (ref "J1") (pin "41") (pinfunction "41_41") (pintype "passive+no_connect"))
    )
    (net (code "101") (name "unconnected-(J1-Pad42)") (class "Default")
      (node (ref "J1") (pin "42") (pinfunction "42_42") (pintype "passive+no_connect"))
    )
    (net (code "102") (name "unconnected-(J1-Pad43)") (class "Default")
      (node (ref "J1") (pin "43") (pinfunction "43_43") (pintype "passive+no_connect"))
    )
    (net (code "103") (name "unconnected-(J1-Pad44)") (class "Default")
      (node (ref "J1") (pin "44") (pinfunction "44_44") (pintype "passive+no_connect"))
    )
    (net (code "104") (name "unconnected-(J1-Pad45)") (class "Default")
      (node (ref "J1") (pin "45") (pinfunction "45_45") (pintype "passive+no_connect"))
    )
    (net (code "105") (name "unconnected-(J1-Pad46)") (class "Default")
      (node (ref "J1") (pin "46") (pinfunction "46_46") (pintype "passive+no_connect"))
    )
    (net (code "106") (name "unconnected-(J1-Pad47)") (class "Default")
      (node (ref "J1") (pin "47") (pinfunction "47_47") (pintype "passive+no_connect"))
    )
    (net (code "107") (name "unconnected-(J1-Pad48)") (class "Default")
      (node (ref "J1") (pin "48") (pinfunction "48_48") (pintype "passive+no_connect"))
    )
    (net (code "108") (name "unconnected-(J1-Pad49)") (class "Default")
      (node (ref "J1") (pin "49") (pinfunction "49_49") (pintype "passive+no_connect"))
    )
    (net (code "109") (name "unconnected-(J1-Pad50)") (class "Default")
      (node (ref "J1") (pin "50") (pinfunction "50_50") (pintype "passive+no_connect"))
    )
    (net (code "110") (name "unconnected-(J1-Pad51)") (class "Default")
      (node (ref "J1") (pin "51") (pinfunction "51_51") (pintype "passive+no_connect"))
    )
    (net (code "111") (name "unconnected-(J1-Pad52)") (class "Default")
      (node (ref "J1") (pin "52") (pinfunction "52_52") (pintype "passive+no_connect"))
    )
    (net (code "112") (name "unconnected-(J1-Pad53)") (class "Default")
      (node (ref "J1") (pin "53") (pinfunction "53_53") (pintype "passive+no_connect"))
    )
    (net (code "113") (name "unconnected-(J1-Pad54)") (class "Default")
      (node (ref "J1") (pin "54") (pinfunction "54_54") (pintype "passive+no_connect"))
    )
    (net (code "114") (name "unconnected-(J1-Pad55)") (class "Default")
      (node (ref "J1") (pin "55") (pinfunction "55_55") (pintype "passive+no_connect"))
    )
    (net (code "115") (name "unconnected-(J1-Pad56)") (class "Default")
      (node (ref "J1") (pin "56") (pinfunction "56_56") (pintype "passive+no_connect"))
    )
    (net (code "116") (name "unconnected-(J1-Pad59)") (class "Default")
      (node (ref "J1") (pin "59") (pinfunction "59_59") (pintype "passive+no_connect"))
    )
    (net (code "117") (name "unconnected-(J1-Pad60)") (class "Default")
      (node (ref "J1") (pin "60") (pinfunction "60_60") (pintype "passive+no_connect"))
    )
    (net (code "118") (name "unconnected-(J1-Pad62)") (class "Default")
      (node (ref "J1") (pin "62") (pinfunction "62_62") (pintype "passive+no_connect"))
    )
    (net (code "119") (name "unconnected-(J1-Pad63)") (class "Default")
      (node (ref "J1") (pin "63") (pinfunction "63_63") (pintype "passive+no_connect"))
    )
    (net (code "120") (name "unconnected-(J1-Pad64)") (class "Default")
      (node (ref "J1") (pin "64") (pinfunction "64_64") (pintype "passive+no_connect"))
    )
    (net (code "121") (name "unconnected-(J1-Pad65)") (class "Default")
      (node (ref "J1") (pin "65") (pinfunction "65_65") (pintype "passive+no_connect"))
    )
    (net (code "122") (name "unconnected-(J1-Pad66)") (class "Default")
      (node (ref "J1") (pin "66") (pinfunction "66_66") (pintype "passive+no_connect"))
    )
    (net (code "123") (name "unconnected-(J1-Pad67)") (class "Default")
      (node (ref "J1") (pin "67") (pinfunction "67_67") (pintype "passive+no_connect"))
    )
    (net (code "124") (name "unconnected-(J1-Pad68)") (class "Default")
      (node (ref "J1") (pin "68") (pinfunction "68_68") (pintype "passive+no_connect"))
    )
    (net (code "125") (name "unconnected-(J1-Pad69)") (class "Default")
      (node (ref "J1") (pin "69") (pinfunction "69_69") (pintype "passive+no_connect"))
    )
    (net (code "126") (name "unconnected-(J1-Pad70)") (class "Default")
      (node (ref "J1") (pin "70") (pinfunction "70_70") (pintype "passive+no_connect"))
    )
    (net (code "127") (name "unconnected-(J1-Pad71)") (class "Default")
      (node (ref "J1") (pin "71") (pinfunction "71_71") (pintype "passive+no_connect"))
    )
    (net (code "128") (name "unconnected-(J1-Pad72)") (class "Default")
      (node (ref "J1") (pin "72") (pinfunction "72_72") (pintype "passive+no_connect"))
    )
    (net (code "129") (name "unconnected-(J1-Pad73)") (class "Default")
      (node (ref "J1") (pin "73") (pinfunction "73_73") (pintype "passive+no_connect"))
    )
    (net (code "130") (name "unconnected-(J1-Pad74)") (class "Default")
      (node (ref "J1") (pin "74") (pinfunction "74_74") (pintype "passive+no_connect"))
    )
    (net (code "131") (name "unconnected-(J1-Pad75)") (class "Default")
      (node (ref "J1") (pin "75") (pinfunction "75_75") (pintype "passive+no_connect"))
    )
    (net (code "132") (name "unconnected-(J1-Pad76)") (class "Default")
      (node (ref "J1") (pin "76") (pinfunction "76_76") (pintype "passive+no_connect"))
    )
    (net (code "133") (name "unconnected-(J1-Pad77)") (class "Default")
      (node (ref "J1") (pin "77") (pinfunction "77_77") (pintype "passive+no_connect"))
    )
    (net (code "134") (name "unconnected-(J1-Pad78)") (class "Default")
      (node (ref "J1") (pin "78") (pinfunction "78_78") (pintype "passive+no_connect"))
    )
    (net (code "135") (name "unconnected-(J1-Pad79)") (class "Default")
      (node (ref "J1") (pin "79") (pinfunction "79_79") (pintype "passive+no_connect"))
    )
    (net (code "136") (name "unconnected-(J1-Pad80)") (class "Default")
      (node (ref "J1") (pin "80") (pinfunction "80_80") (pintype "passive+no_connect"))
    )
    (net (code "137") (name "unconnected-(J1-Pad81)") (class "Default")
      (node (ref "J1") (pin "81") (pinfunction "81_81") (pintype "passive+no_connect"))
    )
    (net (code "138") (name "unconnected-(J1-Pad82)") (class "Default")
      (node (ref "J1") (pin "82") (pinfunction "82_82") (pintype "passive+no_connect"))
    )
    (net (code "139") (name "unconnected-(J1-Pad84)") (class "Default")
      (node (ref "J1") (pin "84") (pinfunction "84_84") (pintype "passive+no_connect"))
    )
    (net (code "140") (name "unconnected-(J1-Pad85)") (class "Default")
      (node (ref "J1") (pin "85") (pinfunction "85_85") (pintype "passive+no_connect"))
    )
    (net (code "141") (name "unconnected-(J1-Pad86)") (class "Default")
      (node (ref "J1") (pin "86") (pinfunction "86_86") (pintype "passive+no_connect"))
    )
    (net (code "142") (name "unconnected-(J1-Pad88)") (class "Default")
      (node (ref "J1") (pin "88") (pinfunction "88_88") (pintype "passive+no_connect"))
    )
    (net (code "143") (name "unconnected-(J1-Pad89)") (class "Default")
      (node (ref "J1") (pin "89") (pinfunction "89_89") (pintype "passive+no_connect"))
    )
    (net (code "144") (name "unconnected-(J1-Pad90)") (class "Default")
      (node (ref "J1") (pin "90") (pinfunction "90_90") (pintype "passive+no_connect"))
    )
    (net (code "145") (name "unconnected-(J1-Pad92)") (class "Default")
      (node (ref "J1") (pin "92") (pinfunction "92_92") (pintype "passive+no_connect"))
    )
    (net (code "146") (name "unconnected-(J1-Pad93)") (class "Default")
      (node (ref "J1") (pin "93") (pinfunction "93_93") (pintype "passive+no_connect"))
    )
    (net (code "147") (name "unconnected-(J1-Pad94)") (class "Default")
      (node (ref "J1") (pin "94") (pinfunction "94_94") (pintype "passive+no_connect"))
    )
    (net (code "148") (name "unconnected-(J1-Pad96)") (class "Default")
      (node (ref "J1") (pin "96") (pinfunction "96_96") (pintype "passive+no_connect"))
    )
    (net (code "149") (name "unconnected-(J1-Pad97)") (class "Default")
      (node (ref "J1") (pin "97") (pinfunction "97_97") (pintype "passive+no_connect"))
    )
    (net (code "150") (name "unconnected-(J1-Pad98)") (class "Default")
      (node (ref "J1") (pin "98") (pinfunction "98_98") (pintype "passive+no_connect"))
    )
    (net (code "151") (name "unconnected-(J1-Pad99)") (class "Default")
      (node (ref "J1") (pin "99") (pinfunction "99_99") (pintype "passive+no_connect"))
    )
    (net (code "152") (name "unconnected-(J1-Pad100)") (class "Default")
      (node (ref "J1") (pin "100") (pinfunction "100_100") (pintype "passive+no_connect"))
    )
    (net (code "153") (name "unconnected-(J1-Pad101)") (class "Default")
      (node (ref "J1") (pin "101") (pinfunction "101_101") (pintype "passive+no_connect"))
    )
    (net (code "154") (name "unconnected-(J1-Pad102)") (class "Default")
      (node (ref "J1") (pin "102") (pinfunction "102_102") (pintype "passive+no_connect"))
    )
    (net (code "155") (name "unconnected-(J1-Pad103)") (class "Default")
      (node (ref "J1") (pin "103") (pinfunction "103_103") (pintype "passive+no_connect"))
    )
    (net (code "156") (name "unconnected-(J1-Pad104)") (class "Default")
      (node (ref "J1") (pin "104") (pinfunction "104_104") (pintype "passive+no_connect"))
    )
    (net (code "157") (name "unconnected-(J2A-SBU1-PadA8)") (class "Default")
      (node (ref "J2") (pin "A8") (pinfunction "SBU1_A8") (pintype "passive"))
    )
    (net (code "158") (name "unconnected-(J2A-SBU2-PadB8)") (class "Default")
      (node (ref "J2") (pin "B8") (pinfunction "SBU2_B8") (pintype "passive"))
    )
    (net (code "159") (name "unconnected-(J23-Pad4)") (class "Default")
      (node (ref "J23") (pin "4") (pinfunction "4_4") (pintype "passive+no_connect"))
    )
    (net (code "160") (name "unconnected-(U1-CAP1_NC-Pad48)") (class "Default")
      (node (ref "U1") (pin "48") (pinfunction "CAP1_NC_48") (pintype "passive+no_connect"))
    )
    (net (code "161") (name "unconnected-(U1-CAP2_NC-Pad47)") (class "Default")
      (node (ref "U1") (pin "47") (pinfunction "CAP2_NC_47") (pintype "passive+no_connect"))
    )
    (net (code "162") (name "unconnected-(U1-IO32-Pad12)") (class "Default")
      (node (ref "U1") (pin "12") (pinfunction "IO32_12") (pintype "bidirectional+no_connect"))
    )
    (net (code "163") (name "unconnected-(U1-IO33-Pad13)") (class "Default")
      (node (ref "U1") (pin "13") (pinfunction "IO33_13") (pintype "bidirectional+no_connect"))
    )
    (net (code "164") (name "unconnected-(U1-LNA_IN-Pad2)") (class "Default")
      (node (ref "U1") (pin "2") (pinfunction "LNA_IN_2") (pintype "bidirectional+no_connect"))
    )
    (net (code "165") (name "unconnected-(U1-VDD_SDIO-Pad26)") (class "Default")
      (node (ref "U1") (pin "26") (pinfunction "VDD_SDIO_26") (pintype "power_in+no_connect"))
    )
    (net (code "166") (name "unconnected-(U1-XTAL_N_NC-Pad44)") (class "Default")
      (node (ref "U1") (pin "44") (pinfunction "XTAL_N_NC_44") (pintype "passive+no_connect"))
    )
    (net (code "167") (name "unconnected-(U1-XTAL_P_NC-Pad45)") (class "Default")
      (node (ref "U1") (pin "45") (pinfunction "XTAL_P_NC_45") (pintype "passive+no_connect"))
    )
    (net (code "168") (name "unconnected-(U2-CHR0-Pad15)") (class "Default")
      (node (ref "U2") (pin "15") (pinfunction "CHR0_15") (pintype "output+no_connect"))
    )
    (net (code "169") (name "unconnected-(U2-CHR1-Pad14)") (class "Default")
      (node (ref "U2") (pin "14") (pinfunction "CHR1_14") (pintype "output+no_connect"))
    )
    (net (code "170") (name "unconnected-(U2-CHREN-Pad13)") (class "Default")
      (node (ref "U2") (pin "13") (pinfunction "CHREN_13") (pintype "output+no_connect"))
    )
    (net (code "171") (name "unconnected-(U2-CTS-Pad23)") (class "Default")
      (node (ref "U2") (pin "23") (pinfunction "CTS_23") (pintype "input+no_connect"))
    )
    (net (code "172") (name "unconnected-(U2-DCD-Pad1)") (class "Default")
      (node (ref "U2") (pin "1") (pinfunction "DCD_1") (pintype "input+no_connect"))
    )
    (net (code "173") (name "unconnected-(U2-DSR-Pad27)") (class "Default")
      (node (ref "U2") (pin "27") (pinfunction "DSR_27") (pintype "input+no_connect"))
    )
    (net (code "174") (name "unconnected-(U2-GPIO.0{slash}TXT-Pad19)") (class "Default")
      (node (ref "U2") (pin "19") (pinfunction "GPIO.0/TXT_19") (pintype "bidirectional+no_connect"))
    )
    (net (code "175") (name "unconnected-(U2-GPIO.1{slash}RXT-Pad18)") (class "Default")
      (node (ref "U2") (pin "18") (pinfunction "GPIO.1/RXT_18") (pintype "bidirectional+no_connect"))
    )
    (net (code "176") (name "unconnected-(U2-GPIO.2{slash}RS485-Pad17)") (class "Default")
      (node (ref "U2") (pin "17") (pinfunction "GPIO.2/RS485_17") (pintype "bidirectional+no_connect"))
    )
    (net (code "177") (name "unconnected-(U2-GPIO.3{slash}WAKEUP-Pad16)") (class "Default")
      (node (ref "U2") (pin "16") (pinfunction "GPIO.3/WAKEUP_16") (pintype "bidirectional+no_connect"))
    )
    (net (code "178") (name "unconnected-(U2-GPIO.4-Pad22)") (class "Default")
      (node (ref "U2") (pin "22") (pinfunction "GPIO.4_22") (pintype "bidirectional+no_connect"))
    )
    (net (code "179") (name "unconnected-(U2-GPIO.5-Pad21)") (class "Default")
      (node (ref "U2") (pin "21") (pinfunction "GPIO.5_21") (pintype "bidirectional+no_connect"))
    )
    (net (code "180") (name "unconnected-(U2-GPIO.6-Pad20)") (class "Default")
      (node (ref "U2") (pin "20") (pinfunction "GPIO.6_20") (pintype "bidirectional+no_connect"))
    )
    (net (code "181") (name "unconnected-(U2-NC-Pad10)") (class "Default")
      (node (ref "U2") (pin "10") (pinfunction "NC_10") (pintype "passive+no_connect"))
    )
    (net (code "182") (name "unconnected-(U2-SUSPEND-Pad12)") (class "Default")
      (node (ref "U2") (pin "12") (pinfunction "SUSPEND_12") (pintype "output+no_connect"))
    )
    (net (code "183") (name "unconnected-(U2-~{RI}{slash}CLK-Pad2)") (class "Default")
      (node (ref "U2") (pin "2") (pinfunction "~{RI}/CLK_2") (pintype "bidirectional+no_connect"))
    )
    (net (code "184") (name "unconnected-(U2-~{SUSPEND}-Pad11)") (class "Default")
      (node (ref "U2") (pin "11") (pinfunction "~{SUSPEND}_11") (pintype "output+no_connect"))
    )
  )
)
